# M1_Design.net
KiCad netlist of a schematic drawn in Altium Designer
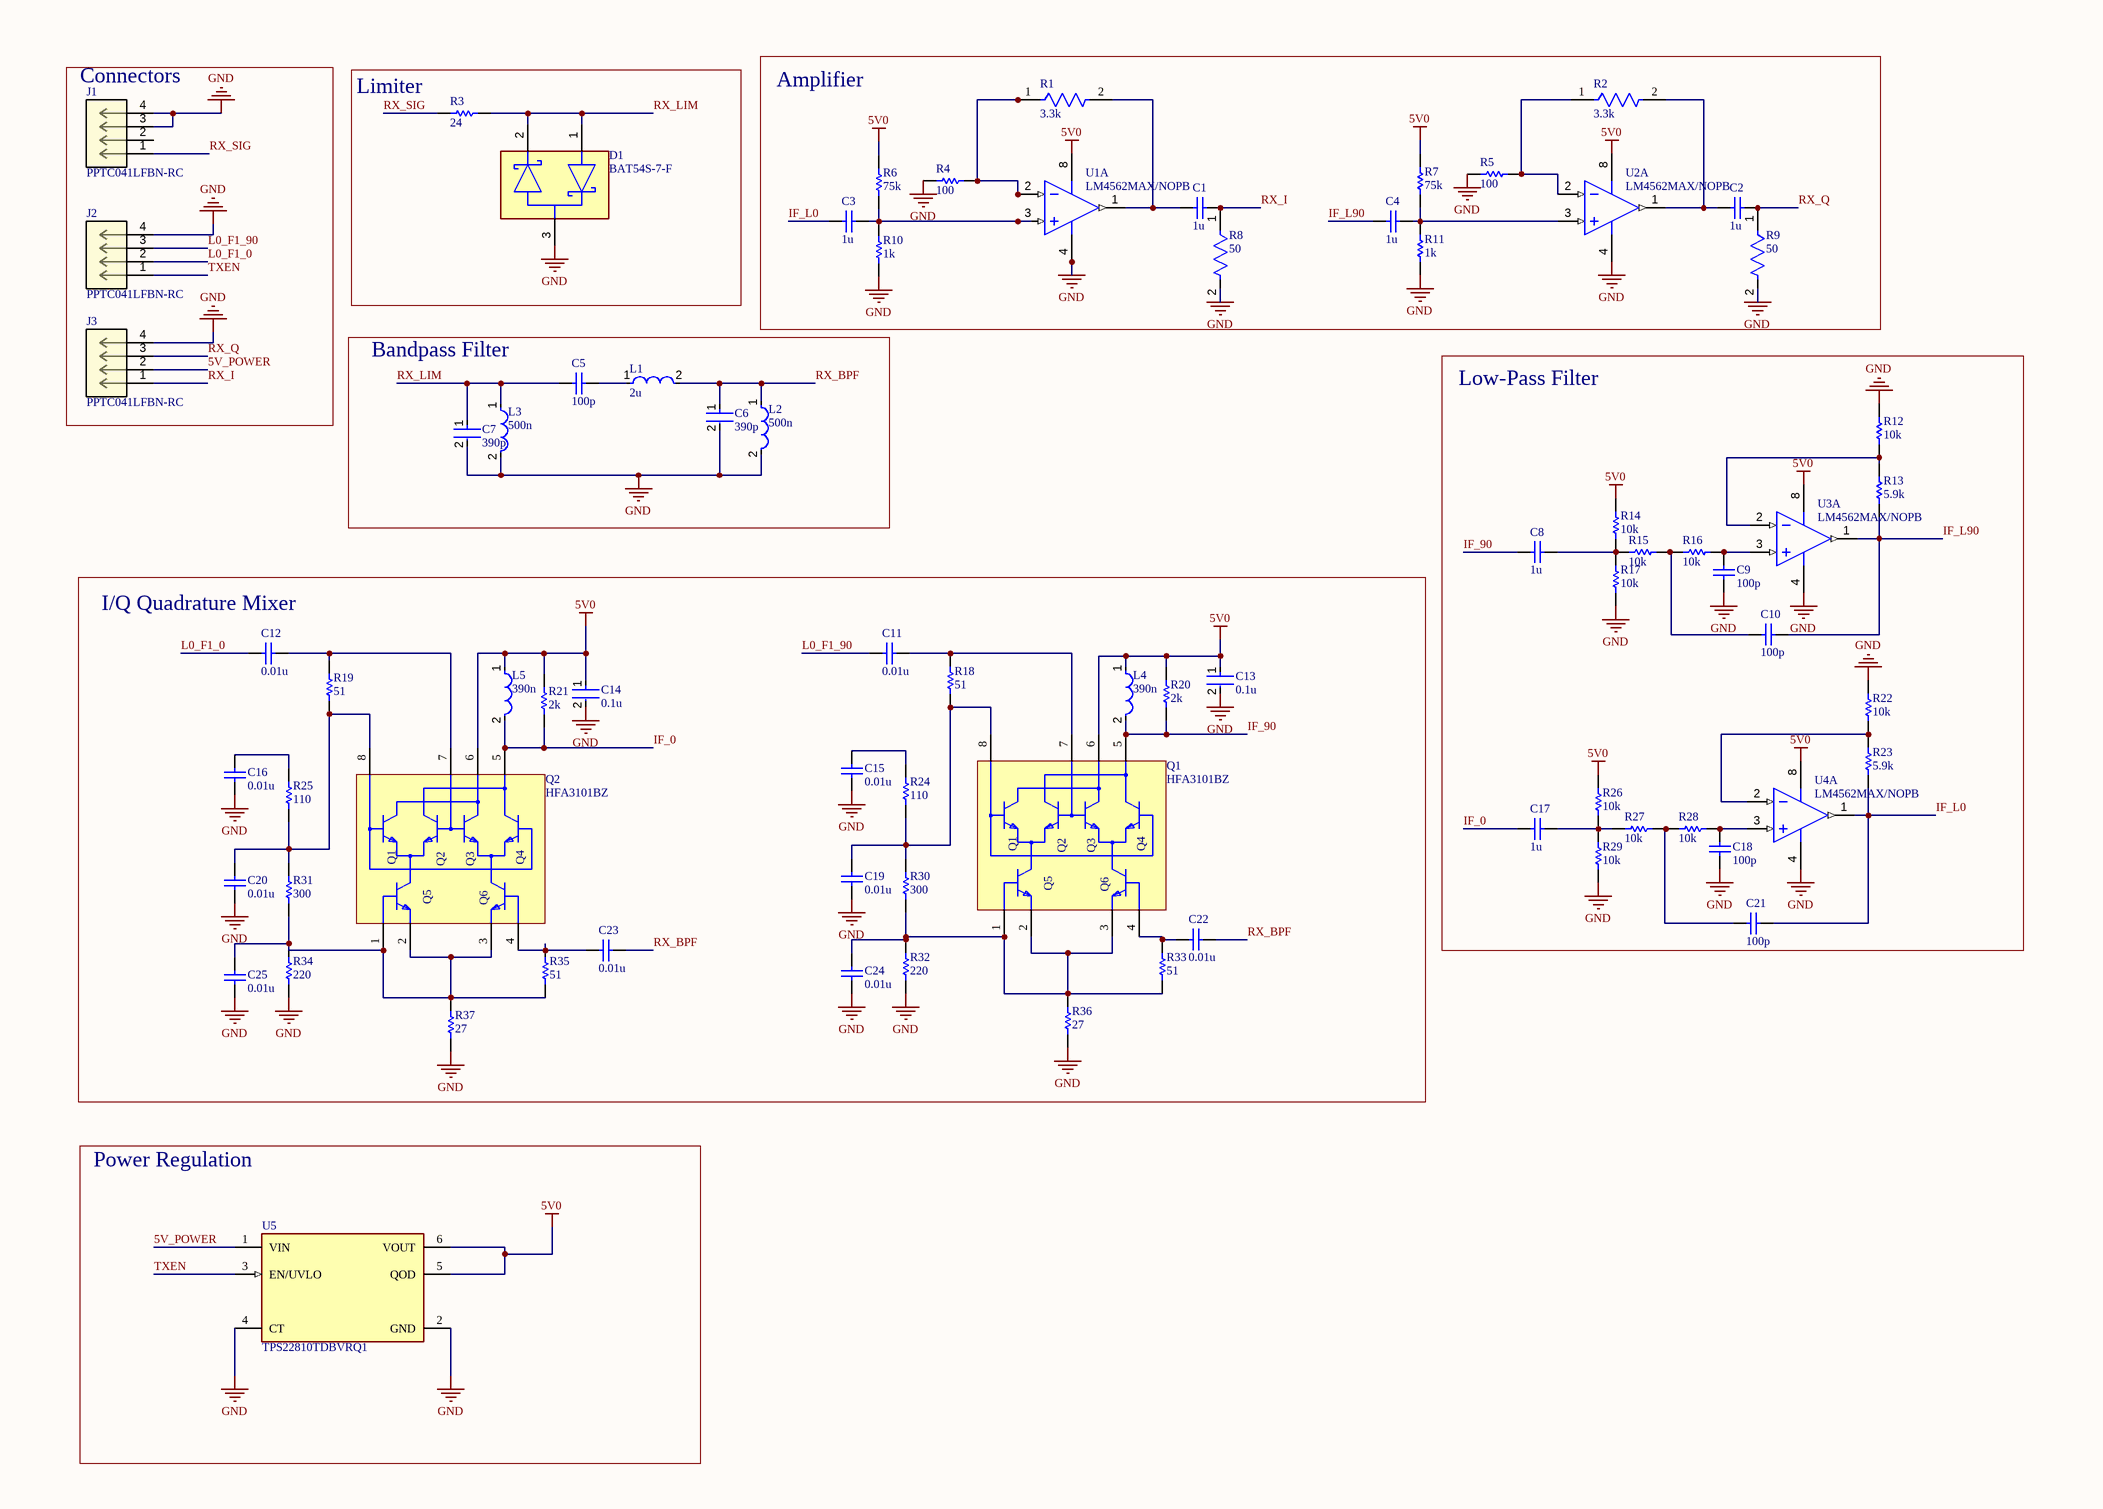
[diagram p0: M1 Design.SchDoc]

(export (version "E")
  (design (tool "Eeschema 10.0.6"))
  (components
    (comp (ref "C1")
      (value "1u")
      (footprint "CAPC3216X110X50LL20T25")
      (description "Chip Capacitor, 1 uF, +/- 10%, 50 V, -55 to 125 degC, 1206 (3216 Metric), RoHS, Tape and Reel")
      (fields (field (name "MANUFACTURER") "Kemet") (field (name "TOLERANCE") "10%"))
      (libsource (lib "Altium Content Vault") (part "CAP-NP-2"))
    )
    (comp (ref "C2")
      (value "1u")
      (footprint "CAPC3216X110X50LL20T25")
      (description "Chip Capacitor, 1 uF, +/- 10%, 50 V, -55 to 125 degC, 1206 (3216 Metric), RoHS, Tape and Reel")
      (fields (field (name "MANUFACTURER") "Kemet") (field (name "TOLERANCE") "10%"))
      (libsource (lib "Altium Content Vault") (part "CAP-NP-2"))
    )
    (comp (ref "C3")
      (value "1u")
      (footprint "CAPC3216X110X50LL20T25")
      (description "Chip Capacitor, 1 uF, +/- 10%, 50 V, -55 to 125 degC, 1206 (3216 Metric), RoHS, Tape and Reel")
      (fields (field (name "MANUFACTURER") "Kemet") (field (name "TOLERANCE") "10%"))
      (libsource (lib "Altium Content Vault") (part "CAP-NP-2"))
    )
    (comp (ref "C4")
      (value "1u")
      (footprint "CAPC3216X110X50LL20T25")
      (description "Chip Capacitor, 1 uF, +/- 10%, 50 V, -55 to 125 degC, 1206 (3216 Metric), RoHS, Tape and Reel")
      (fields (field (name "MANUFACTURER") "Kemet") (field (name "TOLERANCE") "10%"))
      (libsource (lib "Altium Content Vault") (part "CAP-NP-2"))
    )
    (comp (ref "C5")
      (value "100p")
      (footprint "CAPC1608X90X40ML10T20")
      (description "Chip Capacitor, 100 pF, +/- 5%, 50 V, -55 to 125 degC, 0603 (1608 Metric), RoHS, Tape and Reel")
      (fields (field (name "TOLERANCE") "5%") (field (name "VOLTAGE") "50V"))
      (libsource (lib "Altium Content Vault") (part "CAP-NP-2"))
    )
    (comp (ref "C6")
      (value "390p")
      (footprint "FP-GRM155-0_05-MFG")
      (description "Chip Multilayer Ceramic Capacitors for General Purpose, 0402, 390pF, C0G, 30ppm/°C, 5%, 50V")
      (fields (field (name "TOLERANCE") "5%") (field (name "VOLTAGE") "50V"))
      (libsource (lib "Altium Content Vault") (part "02cd4be3c70576c341d710602a673aa"))
    )
    (comp (ref "C7")
      (value "390p")
      (footprint "FP-GRM155-0_05-MFG")
      (description "Chip Multilayer Ceramic Capacitors for General Purpose, 0402, 390pF, C0G, 30ppm/°C, 5%, 50V")
      (fields (field (name "TOLERANCE") "5%") (field (name "VOLTAGE") "50V"))
      (libsource (lib "Altium Content Vault") (part "02cd4be3c70576c341d710602a673aa"))
    )
    (comp (ref "C8")
      (value "1u")
      (footprint "CAPC3216X110X50LL20T25")
      (description "Chip Capacitor, 1 uF, +/- 10%, 50 V, -55 to 125 degC, 1206 (3216 Metric), RoHS, Tape and Reel")
      (fields (field (name "MANUFACTURER") "Kemet") (field (name "TOLERANCE") "10%"))
      (libsource (lib "Altium Content Vault") (part "CAP-NP-2"))
    )
    (comp (ref "C9")
      (value "100p")
      (footprint "CAPC1608X90X40ML10T20")
      (description "Chip Capacitor, 100 pF, +/- 5%, 50 V, -55 to 125 degC, 0603 (1608 Metric), RoHS, Tape and Reel")
      (fields (field (name "TOLERANCE") "5%") (field (name "VOLTAGE") "50V"))
      (libsource (lib "Altium Content Vault") (part "CAP-NP-2"))
    )
    (comp (ref "C10")
      (value "100p")
      (footprint "CAPC1608X90X40ML10T20")
      (description "Chip Capacitor, 100 pF, +/- 5%, 50 V, -55 to 125 degC, 0603 (1608 Metric), RoHS, Tape and Reel")
      (fields (field (name "TOLERANCE") "5%") (field (name "VOLTAGE") "50V"))
      (libsource (lib "Altium Content Vault") (part "CAP-NP-2"))
    )
    (comp (ref "C11")
      (value "0.01u")
      (footprint "CAPC1005X55X25LL05T10")
      (description "Chip Capacitor, 10 nF, 16 V, 10%, -55 to 125 degC, 0402 (1005 Metric), RoHS, Tape and Reel")
      (fields (field (name "MANUFACTURER") "Murata"))
      (libsource (lib "Altium Content Vault") (part "CAP-NP-2"))
    )
    (comp (ref "C12")
      (value "0.01u")
      (footprint "CAPC1005X55X25LL05T10")
      (description "Chip Capacitor, 10 nF, 16 V, 10%, -55 to 125 degC, 0402 (1005 Metric), RoHS, Tape and Reel")
      (fields (field (name "MANUFACTURER") "Murata"))
      (libsource (lib "Altium Content Vault") (part "CAP-NP-2"))
    )
    (comp (ref "C13")
      (value "0.1u")
      (footprint "FP-CL17-IPC_C")
      (description "Cap Ceramic 100nF 10V X7R ±10% SMD 0402 +125°C Paper T/R")
      (fields (field (name "TOLERANCE") "10%"))
      (libsource (lib "Altium Content Vault") (part "b4654b650e69147ec39a6b967a45e02"))
    )
    (comp (ref "C14")
      (value "0.1u")
      (footprint "FP-CL17-IPC_C")
      (description "Cap Ceramic 100nF 10V X7R ±10% SMD 0402 +125°C Paper T/R")
      (fields (field (name "TOLERANCE") "10%"))
      (libsource (lib "Altium Content Vault") (part "b4654b650e69147ec39a6b967a45e02"))
    )
    (comp (ref "C15")
      (value "0.01u")
      (footprint "CAPC1005X55X25LL05T10")
      (description "Chip Capacitor, 10 nF, 16 V, 10%, -55 to 125 degC, 0402 (1005 Metric), RoHS, Tape and Reel")
      (fields (field (name "MANUFACTURER") "Murata"))
      (libsource (lib "Altium Content Vault") (part "CAP-NP-2"))
    )
    (comp (ref "C16")
      (value "0.01u")
      (footprint "CAPC1005X55X25LL05T10")
      (description "Chip Capacitor, 10 nF, 16 V, 10%, -55 to 125 degC, 0402 (1005 Metric), RoHS, Tape and Reel")
      (fields (field (name "MANUFACTURER") "Murata"))
      (libsource (lib "Altium Content Vault") (part "CAP-NP-2"))
    )
    (comp (ref "C17")
      (value "1u")
      (footprint "CAPC3216X110X50LL20T25")
      (description "Chip Capacitor, 1 uF, +/- 10%, 50 V, -55 to 125 degC, 1206 (3216 Metric), RoHS, Tape and Reel")
      (fields (field (name "MANUFACTURER") "Kemet") (field (name "TOLERANCE") "10%"))
      (libsource (lib "Altium Content Vault") (part "CAP-NP-2"))
    )
    (comp (ref "C18")
      (value "100p")
      (footprint "CAPC1608X90X40ML10T20")
      (description "Chip Capacitor, 100 pF, +/- 5%, 50 V, -55 to 125 degC, 0603 (1608 Metric), RoHS, Tape and Reel")
      (fields (field (name "TOLERANCE") "5%") (field (name "VOLTAGE") "50V"))
      (libsource (lib "Altium Content Vault") (part "CAP-NP-2"))
    )
    (comp (ref "C19")
      (value "0.01u")
      (footprint "CAPC1005X55X25LL05T10")
      (description "Chip Capacitor, 10 nF, 16 V, 10%, -55 to 125 degC, 0402 (1005 Metric), RoHS, Tape and Reel")
      (fields (field (name "MANUFACTURER") "Murata"))
      (libsource (lib "Altium Content Vault") (part "CAP-NP-2"))
    )
    (comp (ref "C20")
      (value "0.01u")
      (footprint "CAPC1005X55X25LL05T10")
      (description "Chip Capacitor, 10 nF, 16 V, 10%, -55 to 125 degC, 0402 (1005 Metric), RoHS, Tape and Reel")
      (fields (field (name "MANUFACTURER") "Murata"))
      (libsource (lib "Altium Content Vault") (part "CAP-NP-2"))
    )
    (comp (ref "C21")
      (value "100p")
      (footprint "CAPC1608X90X40ML10T20")
      (description "Chip Capacitor, 100 pF, +/- 5%, 50 V, -55 to 125 degC, 0603 (1608 Metric), RoHS, Tape and Reel")
      (fields (field (name "TOLERANCE") "5%") (field (name "VOLTAGE") "50V"))
      (libsource (lib "Altium Content Vault") (part "CAP-NP-2"))
    )
    (comp (ref "C22")
      (value "0.01u")
      (footprint "CAPC1005X55X25LL05T10")
      (description "Chip Capacitor, 10 nF, 16 V, 10%, -55 to 125 degC, 0402 (1005 Metric), RoHS, Tape and Reel")
      (fields (field (name "MANUFACTURER") "Murata"))
      (libsource (lib "Altium Content Vault") (part "CAP-NP-2"))
    )
    (comp (ref "C23")
      (value "0.01u")
      (footprint "CAPC1005X55X25LL05T10")
      (description "Chip Capacitor, 10 nF, 16 V, 10%, -55 to 125 degC, 0402 (1005 Metric), RoHS, Tape and Reel")
      (fields (field (name "MANUFACTURER") "Murata"))
      (libsource (lib "Altium Content Vault") (part "CAP-NP-2"))
    )
    (comp (ref "C24")
      (value "0.01u")
      (footprint "CAPC1005X55X25LL05T10")
      (description "Chip Capacitor, 10 nF, 16 V, 10%, -55 to 125 degC, 0402 (1005 Metric), RoHS, Tape and Reel")
      (fields (field (name "MANUFACTURER") "Murata"))
      (libsource (lib "Altium Content Vault") (part "CAP-NP-2"))
    )
    (comp (ref "C25")
      (value "0.01u")
      (footprint "CAPC1005X55X25LL05T10")
      (description "Chip Capacitor, 10 nF, 16 V, 10%, -55 to 125 degC, 0402 (1005 Metric), RoHS, Tape and Reel")
      (fields (field (name "MANUFACTURER") "Murata"))
      (libsource (lib "Altium Content Vault") (part "CAP-NP-2"))
    )
    (comp (ref "D1")
      (value "BAT54S-7-F")
      (footprint "FP-SOT23-MFG")
      (description "DIODE ARRAY SCHOTTKY 30V SOT23-3")
      (libsource (lib "Altium Content Vault") (part "835e4e71cf852b8cae3cf70bf14abf8"))
    )
    (comp (ref "J1")
      (value "PPTC041LFBN-RC")
      (footprint "CONN_PPTC041LFBN-RC_SUL")
      (description "No Description Available")
      (libsource (lib "PPTC041LFBN-RC") (part "PPTC041LFBN-RC"))
    )
    (comp (ref "J2")
      (value "PPTC041LFBN-RC")
      (footprint "CONN_PPTC041LFBN-RC_SUL")
      (description "No Description Available")
      (libsource (lib "PPTC041LFBN-RC") (part "PPTC041LFBN-RC"))
    )
    (comp (ref "J3")
      (value "PPTC041LFBN-RC")
      (footprint "CONN_PPTC041LFBN-RC_SUL")
      (description "No Description Available")
      (libsource (lib "PPTC041LFBN-RC") (part "PPTC041LFBN-RC"))
    )
    (comp (ref "L1")
      (value "2u")
      (footprint "FP-LQW15CA_00-MFG")
      (description "Wire Wound Ferrite Inductor for General Circuits 2000nH ±10% 130mA 3.2Ω 0402 (1005)")
      (fields (field (name "TOLERANCE") "10%"))
      (libsource (lib "Altium Content Vault") (part "725321dda6339637d4d059423bc1c3c"))
    )
    (comp (ref "L2")
      (value "500n")
      (footprint "FP-LQW15CA_00-MFG")
      (description "Wire Wound Ferrite Inductor for General Circuits 500nH ±5% 270mA 0.97Ω 0402 (1005)")
      (fields (field (name "TOLERANCE") "5%"))
      (libsource (lib "Altium Content Vault") (part "725321dda6339637d4d059423bc1c3c"))
    )
    (comp (ref "L3")
      (value "500n")
      (footprint "FP-LQW15CA_00-MFG")
      (description "Wire Wound Ferrite Inductor for General Circuits 500nH ±5% 270mA 0.97Ω 0402 (1005)")
      (fields (field (name "TOLERANCE") "5%"))
      (libsource (lib "Altium Content Vault") (part "725321dda6339637d4d059423bc1c3c"))
    )
    (comp (ref "L4")
      (value "390n")
      (footprint "FP-LQW18AN_00-MFG")
      (description "Wire Wound RF Inductor 390nH ±5% 80mA 6.2Ω 0603 (1608)")
      (fields (field (name "TOLERANCE") "5%"))
      (libsource (lib "Altium Content Vault") (part "725321dda6339637d4d059423bc1c3c"))
    )
    (comp (ref "L5")
      (value "390n")
      (footprint "FP-LQW18AN_00-MFG")
      (description "Wire Wound RF Inductor 390nH ±5% 80mA 6.2Ω 0603 (1608)")
      (fields (field (name "TOLERANCE") "5%"))
      (libsource (lib "Altium Content Vault") (part "725321dda6339637d4d059423bc1c3c"))
    )
    (comp (ref "Q1")
      (value "HFA3101BZ")
      (footprint "M8_15_MFG")
      (description "HFA3096 Series NPN 12 Vce 10 Ghz UHF Transistor Array - SOIC-8")
      (libsource (lib "Altium Content Vault") (part "bc79141c5fe5962b3618e6c48c8dfa3"))
    )
    (comp (ref "Q2")
      (value "HFA3101BZ")
      (footprint "M8_15_MFG")
      (description "HFA3096 Series NPN 12 Vce 10 Ghz UHF Transistor Array - SOIC-8")
      (libsource (lib "Altium Content Vault") (part "bc79141c5fe5962b3618e6c48c8dfa3"))
    )
    (comp (ref "R1")
      (value "3.3k")
      (footprint "FP-ERA2A-MFG")
      (fields (field (name "TOLERANCE") "0.1%"))
      (libsource (lib "Altium Content Vault") (part "1029c3af85768c4190bb7ad29bc67b5"))
    )
    (comp (ref "R2")
      (value "3.3k")
      (footprint "FP-ERA2A-MFG")
      (fields (field (name "TOLERANCE") "0.1%"))
      (libsource (lib "Altium Content Vault") (part "1029c3af85768c4190bb7ad29bc67b5"))
    )
    (comp (ref "R3")
      (value "24")
      (footprint "RESC1005X40X25LL05T10")
      (fields (field (name "PART NUMBER") "RC0402JR-0724RL") (field (name "MANUFACTURER") "Yageo"))
      (libsource (lib "Altium Content Vault") (part "RES"))
    )
    (comp (ref "R4")
      (value "100")
      (footprint "RESC1005X40X25NL05T10")
      (fields (field (name "PART NUMBER") "RC0402JR-07100RL") (field (name "MANUFACTURER") "Yageo / Phycomp"))
      (libsource (lib "Altium Content Vault") (part "RES"))
    )
    (comp (ref "R5")
      (value "100")
      (footprint "RESC1005X40X25NL05T10")
      (fields (field (name "PART NUMBER") "RC0402JR-07100RL") (field (name "MANUFACTURER") "Yageo / Phycomp"))
      (libsource (lib "Altium Content Vault") (part "RES"))
    )
    (comp (ref "R6")
      (value "75k")
      (footprint "RESC1005X40X25NL10T10")
      (fields (field (name "PART NUMBER") "ERA-2AEB753X") (field (name "MANUFACTURER") "Panasonic"))
      (libsource (lib "Altium Content Vault") (part "RES"))
    )
    (comp (ref "R7")
      (value "75k")
      (footprint "RESC1005X40X25NL10T10")
      (fields (field (name "PART NUMBER") "ERA-2AEB753X") (field (name "MANUFACTURER") "Panasonic"))
      (libsource (lib "Altium Content Vault") (part "RES"))
    )
    (comp (ref "R8")
      (value "50")
      (footprint "FP-ALN2512-MFG")
      (description "2512 CHIP ALNI 50 OHMS 1%")
      (libsource (lib "Altium Content Vault") (part "1029c3af85768c4190bb7ad29bc67b5"))
    )
    (comp (ref "R9")
      (value "50")
      (footprint "FP-ALN2512-MFG")
      (description "2512 CHIP ALNI 50 OHMS 1%")
      (libsource (lib "Altium Content Vault") (part "1029c3af85768c4190bb7ad29bc67b5"))
    )
    (comp (ref "R10")
      (value "1k")
      (footprint "RESC1005X40X25LL05T10")
      (fields (field (name "PART NUMBER") "RC0402JR-071KL") (field (name "MANUFACTURER") "Yageo / Phycomp"))
      (libsource (lib "Altium Content Vault") (part "RES"))
    )
    (comp (ref "R11")
      (value "1k")
      (footprint "RESC1005X40X25LL05T10")
      (fields (field (name "PART NUMBER") "RC0402JR-071KL") (field (name "MANUFACTURER") "Yageo / Phycomp"))
      (libsource (lib "Altium Content Vault") (part "RES"))
    )
    (comp (ref "R12")
      (value "10k")
      (footprint "RESC1005X40X25LL05T10")
      (fields (field (name "PART NUMBER") "RC0402FR-0710KL") (field (name "MANUFACTURER") "Yageo / Phycomp"))
      (libsource (lib "Altium Content Vault") (part "RES"))
    )
    (comp (ref "R13")
      (value "5.9k")
      (footprint "RESC1608X55X30LL15T15")
      (fields (field (name "PART NUMBER") "ERJ-3EKF5901V") (field (name "MANUFACTURER") "Panasonic"))
      (libsource (lib "Altium Content Vault") (part "RES"))
    )
    (comp (ref "R14")
      (value "10k")
      (footprint "RESC1005X40X25LL05T10")
      (fields (field (name "PART NUMBER") "RC0402FR-0710KL") (field (name "MANUFACTURER") "Yageo / Phycomp"))
      (libsource (lib "Altium Content Vault") (part "RES"))
    )
    (comp (ref "R15")
      (value "10k")
      (footprint "RESC1005X40X25LL05T10")
      (fields (field (name "PART NUMBER") "RC0402FR-0710KL") (field (name "MANUFACTURER") "Yageo / Phycomp"))
      (libsource (lib "Altium Content Vault") (part "RES"))
    )
    (comp (ref "R16")
      (value "10k")
      (footprint "RESC1005X40X25LL05T10")
      (fields (field (name "PART NUMBER") "RC0402FR-0710KL") (field (name "MANUFACTURER") "Yageo / Phycomp"))
      (libsource (lib "Altium Content Vault") (part "RES"))
    )
    (comp (ref "R17")
      (value "10k")
      (footprint "RESC1005X40X25LL05T10")
      (fields (field (name "PART NUMBER") "RC0402FR-0710KL") (field (name "MANUFACTURER") "Yageo / Phycomp"))
      (libsource (lib "Altium Content Vault") (part "RES"))
    )
    (comp (ref "R18")
      (value "51")
      (footprint "RESC1005X40X25ML05T10")
      (fields (field (name "MANUFACTURER") "Yageo / Phycomp") (field (name "PART NUMBER") "RC0402JR-0751RL"))
      (libsource (lib "Altium Content Vault") (part "RES"))
    )
    (comp (ref "R19")
      (value "51")
      (footprint "RESC1005X40X25ML05T10")
      (fields (field (name "MANUFACTURER") "Yageo / Phycomp") (field (name "PART NUMBER") "RC0402JR-0751RL"))
      (libsource (lib "Altium Content Vault") (part "RES"))
    )
    (comp (ref "R20")
      (value "2k")
      (footprint "RESC1005X40X25LL10T10")
      (fields (field (name "MANUFACTURER") "Panasonic") (field (name "PART NUMBER") "ERA-2AEB202X"))
      (libsource (lib "Altium Content Vault") (part "RES"))
    )
    (comp (ref "R21")
      (value "2k")
      (footprint "RESC1005X40X25LL10T10")
      (fields (field (name "MANUFACTURER") "Panasonic") (field (name "PART NUMBER") "ERA-2AEB202X"))
      (libsource (lib "Altium Content Vault") (part "RES"))
    )
    (comp (ref "R22")
      (value "10k")
      (footprint "RESC1005X40X25LL05T10")
      (fields (field (name "PART NUMBER") "RC0402FR-0710KL") (field (name "MANUFACTURER") "Yageo / Phycomp"))
      (libsource (lib "Altium Content Vault") (part "RES"))
    )
    (comp (ref "R23")
      (value "5.9k")
      (footprint "RESC1608X55X30LL15T15")
      (fields (field (name "PART NUMBER") "ERJ-3EKF5901V") (field (name "MANUFACTURER") "Panasonic"))
      (libsource (lib "Altium Content Vault") (part "RES"))
    )
    (comp (ref "R24")
      (value "110")
      (footprint "RESC1005X40X25ML05T05")
      (fields (field (name "MANUFACTURER") "Panasonic") (field (name "PART NUMBER") "ERJ-2GEJ111X"))
      (libsource (lib "Altium Content Vault") (part "RES"))
    )
    (comp (ref "R25")
      (value "110")
      (footprint "RESC1005X40X25ML05T05")
      (fields (field (name "MANUFACTURER") "Panasonic") (field (name "PART NUMBER") "ERJ-2GEJ111X"))
      (libsource (lib "Altium Content Vault") (part "RES"))
    )
    (comp (ref "R26")
      (value "10k")
      (footprint "RESC1005X40X25LL05T10")
      (fields (field (name "PART NUMBER") "RC0402FR-0710KL") (field (name "MANUFACTURER") "Yageo / Phycomp"))
      (libsource (lib "Altium Content Vault") (part "RES"))
    )
    (comp (ref "R27")
      (value "10k")
      (footprint "RESC1005X40X25LL05T10")
      (fields (field (name "PART NUMBER") "RC0402FR-0710KL") (field (name "MANUFACTURER") "Yageo / Phycomp"))
      (libsource (lib "Altium Content Vault") (part "RES"))
    )
    (comp (ref "R28")
      (value "10k")
      (footprint "RESC1005X40X25LL05T10")
      (fields (field (name "PART NUMBER") "RC0402FR-0710KL") (field (name "MANUFACTURER") "Yageo / Phycomp"))
      (libsource (lib "Altium Content Vault") (part "RES"))
    )
    (comp (ref "R29")
      (value "10k")
      (footprint "RESC1005X40X25LL05T10")
      (fields (field (name "PART NUMBER") "RC0402FR-0710KL") (field (name "MANUFACTURER") "Yageo / Phycomp"))
      (libsource (lib "Altium Content Vault") (part "RES"))
    )
    (comp (ref "R30")
      (value "300")
      (footprint "RESC1608X55X25LL10T15")
      (fields (field (name "MANUFACTURER") "Yageo"))
      (libsource (lib "Altium Content Vault") (part "RES-2"))
    )
    (comp (ref "R31")
      (value "300")
      (footprint "RESC1608X55X25LL10T15")
      (fields (field (name "MANUFACTURER") "Yageo"))
      (libsource (lib "Altium Content Vault") (part "RES-2"))
    )
    (comp (ref "R32")
      (value "220")
      (footprint "RESC1005X40X25NL05T10")
      (fields (field (name "MANUFACTURER") "Yageo / Phycomp") (field (name "PART NUMBER") "RC0402JR-07220RL"))
      (libsource (lib "Altium Content Vault") (part "RES"))
    )
    (comp (ref "R33")
      (value "51")
      (footprint "RESC1005X40X25ML05T10")
      (fields (field (name "MANUFACTURER") "Yageo / Phycomp") (field (name "PART NUMBER") "RC0402JR-0751RL"))
      (libsource (lib "Altium Content Vault") (part "RES"))
    )
    (comp (ref "R34")
      (value "220")
      (footprint "RESC1005X40X25NL05T10")
      (fields (field (name "MANUFACTURER") "Yageo / Phycomp") (field (name "PART NUMBER") "RC0402JR-07220RL"))
      (libsource (lib "Altium Content Vault") (part "RES"))
    )
    (comp (ref "R35")
      (value "51")
      (footprint "RESC1005X40X25ML05T10")
      (fields (field (name "MANUFACTURER") "Yageo / Phycomp") (field (name "PART NUMBER") "RC0402JR-0751RL"))
      (libsource (lib "Altium Content Vault") (part "RES"))
    )
    (comp (ref "R36")
      (value "27")
      (footprint "RESC1005X40X25NL05T10")
      (fields (field (name "PART NUMBER") "RC0402JR-0727RL") (field (name "MANUFACTURER") "Yageo / Phycomp"))
      (libsource (lib "Altium Content Vault") (part "RES"))
    )
    (comp (ref "R37")
      (value "27")
      (footprint "RESC1005X40X25NL05T10")
      (fields (field (name "PART NUMBER") "RC0402JR-0727RL") (field (name "MANUFACTURER") "Yageo / Phycomp"))
      (libsource (lib "Altium Content Vault") (part "RES"))
    )
    (comp (ref "U1")
      (value "LM4562MAX/NOPB")
      (footprint "D0008A_N")
      (description "Dual High Performance, High Fidelity Audio Operational Amplifier, 8-pin Narrow SOIC, Pb-Free")
      (fields (field (name "MANUFACTURER") "Texas Instruments"))
      (libsource (lib "Altium Content Vault") (part "AMP-AUDA-LM4562-8"))
    )
    (comp (ref "U2")
      (value "LM4562MAX/NOPB")
      (footprint "D0008A_N")
      (description "Dual High Performance, High Fidelity Audio Operational Amplifier, 8-pin Narrow SOIC, Pb-Free")
      (fields (field (name "MANUFACTURER") "Texas Instruments"))
      (libsource (lib "Altium Content Vault") (part "AMP-AUDA-LM4562-8"))
    )
    (comp (ref "U3")
      (value "LM4562MAX/NOPB")
      (footprint "D0008A_N")
      (description "Dual High Performance, High Fidelity Audio Operational Amplifier, 8-pin Narrow SOIC, Pb-Free")
      (fields (field (name "MANUFACTURER") "Texas Instruments"))
      (libsource (lib "Altium Content Vault") (part "AMP-AUDA-LM4562-8"))
    )
    (comp (ref "U4")
      (value "LM4562MAX/NOPB")
      (footprint "D0008A_N")
      (description "Dual High Performance, High Fidelity Audio Operational Amplifier, 8-pin Narrow SOIC, Pb-Free")
      (fields (field (name "MANUFACTURER") "Texas Instruments"))
      (libsource (lib "Altium Content Vault") (part "AMP-AUDA-LM4562-8"))
    )
    (comp (ref "U5")
      (value "TPS22810TDBVRQ1")
      (footprint "FP-DBV0006A-MFG")
      (description "IC PWR SWITCH N-CHAN 1:1 SOT23-6")
      (libsource (lib "Altium Content Vault") (part "2d4a2501f31e6718a49a06b44f8b6c7"))
    )
  )
  (nets
    (net (code "1") (name "/5V_POWER") (class "Default")
      (node (ref "J3") (pin "2") (pinfunction "2_2") (pintype "passive"))
      (node (ref "U5") (pin "1") (pinfunction "VIN_1") (pintype "power_in"))
    )
    (net (code "2") (name "/IF_0") (class "Default")
      (node (ref "C17") (pin "1") (pinfunction "1_1") (pintype "passive"))
      (node (ref "L5") (pin "2") (pinfunction "2_2") (pintype "passive"))
      (node (ref "Q2") (pin "5") (pinfunction "C2_C4_5") (pintype "passive"))
      (node (ref "R21") (pin "1") (pinfunction "1_1") (pintype "passive"))
    )
    (net (code "3") (name "/IF_90") (class "Default")
      (node (ref "C8") (pin "1") (pinfunction "1_1") (pintype "passive"))
      (node (ref "L4") (pin "2") (pinfunction "2_2") (pintype "passive"))
      (node (ref "Q1") (pin "5") (pinfunction "C2_C4_5") (pintype "passive"))
      (node (ref "R20") (pin "1") (pinfunction "1_1") (pintype "passive"))
    )
    (net (code "4") (name "/IF_L0") (class "Default")
      (node (ref "C21") (pin "2") (pinfunction "2_2") (pintype "passive"))
      (node (ref "C3") (pin "1") (pinfunction "1_1") (pintype "passive"))
      (node (ref "R23") (pin "1") (pinfunction "1_1") (pintype "passive"))
      (node (ref "U4") (pin "1") (pinfunction "OUT_A_1") (pintype "output"))
    )
    (net (code "5") (name "/IF_L90") (class "Default")
      (node (ref "C10") (pin "2") (pinfunction "2_2") (pintype "passive"))
      (node (ref "C4") (pin "1") (pinfunction "1_1") (pintype "passive"))
      (node (ref "R13") (pin "1") (pinfunction "1_1") (pintype "passive"))
      (node (ref "U3") (pin "1") (pinfunction "OUT_A_1") (pintype "output"))
    )
    (net (code "6") (name "/L0_F1_0") (class "Default")
      (node (ref "C12") (pin "1") (pinfunction "1_1") (pintype "passive"))
      (node (ref "J2") (pin "2") (pinfunction "2_2") (pintype "passive"))
    )
    (net (code "7") (name "/L0_F1_90") (class "Default")
      (node (ref "C11") (pin "1") (pinfunction "1_1") (pintype "passive"))
      (node (ref "J2") (pin "3") (pinfunction "3_3") (pintype "passive"))
    )
    (net (code "8") (name "/RX_BPF") (class "Default")
      (node (ref "C22") (pin "1") (pinfunction "1_1") (pintype "passive"))
      (node (ref "C23") (pin "1") (pinfunction "1_1") (pintype "passive"))
      (node (ref "C6") (pin "1") (pinfunction "1_1") (pintype "passive"))
      (node (ref "L1") (pin "2") (pinfunction "2_2") (pintype "passive"))
      (node (ref "L2") (pin "1") (pinfunction "1_1") (pintype "passive"))
    )
    (net (code "9") (name "/RX_I") (class "Default")
      (node (ref "C1") (pin "2") (pinfunction "2_2") (pintype "passive"))
      (node (ref "J3") (pin "1") (pinfunction "1_1") (pintype "passive"))
      (node (ref "R8") (pin "1") (pinfunction "1_1") (pintype "passive"))
    )
    (net (code "10") (name "/RX_LIM") (class "Default")
      (node (ref "C5") (pin "1") (pinfunction "1_1") (pintype "passive"))
      (node (ref "C7") (pin "1") (pinfunction "1_1") (pintype "passive"))
      (node (ref "D1") (pin "1") (pinfunction "1_1") (pintype "passive"))
      (node (ref "D1") (pin "2") (pinfunction "2_2") (pintype "passive"))
      (node (ref "L3") (pin "1") (pinfunction "1_1") (pintype "passive"))
      (node (ref "R3") (pin "2") (pinfunction "2_2") (pintype "passive"))
    )
    (net (code "11") (name "/RX_Q") (class "Default")
      (node (ref "C2") (pin "2") (pinfunction "2_2") (pintype "passive"))
      (node (ref "J3") (pin "3") (pinfunction "3_3") (pintype "passive"))
      (node (ref "R9") (pin "1") (pinfunction "1_1") (pintype "passive"))
    )
    (net (code "12") (name "/RX_SIG") (class "Default")
      (node (ref "J1") (pin "1") (pinfunction "1_1") (pintype "passive"))
      (node (ref "R3") (pin "1") (pinfunction "1_1") (pintype "passive"))
    )
    (net (code "13") (name "/TXEN") (class "Default")
      (node (ref "J2") (pin "1") (pinfunction "1_1") (pintype "passive"))
      (node (ref "U5") (pin "3") (pinfunction "EN/UVLO_3") (pintype "input"))
    )
    (net (code "14") (name "5V0") (class "Default")
      (node (ref "C13") (pin "1") (pinfunction "1_1") (pintype "passive"))
      (node (ref "C14") (pin "1") (pinfunction "1_1") (pintype "passive"))
      (node (ref "L4") (pin "1") (pinfunction "1_1") (pintype "passive"))
      (node (ref "L5") (pin "1") (pinfunction "1_1") (pintype "passive"))
      (node (ref "Q1") (pin "6") (pinfunction "C1_C3_6") (pintype "passive"))
      (node (ref "Q2") (pin "6") (pinfunction "C1_C3_6") (pintype "passive"))
      (node (ref "R14") (pin "2") (pinfunction "2_2") (pintype "passive"))
      (node (ref "R20") (pin "2") (pinfunction "2_2") (pintype "passive"))
      (node (ref "R21") (pin "2") (pinfunction "2_2") (pintype "passive"))
      (node (ref "R26") (pin "2") (pinfunction "2_2") (pintype "passive"))
      (node (ref "R6") (pin "2") (pinfunction "2_2") (pintype "passive"))
      (node (ref "R7") (pin "2") (pinfunction "2_2") (pintype "passive"))
      (node (ref "U1") (pin "8") (pinfunction "V+_8") (pintype "power_in"))
      (node (ref "U2") (pin "8") (pinfunction "V+_8") (pintype "power_in"))
      (node (ref "U3") (pin "8") (pinfunction "V+_8") (pintype "power_in"))
      (node (ref "U4") (pin "8") (pinfunction "V+_8") (pintype "power_in"))
      (node (ref "U5") (pin "5") (pinfunction "QOD_5") (pintype "passive"))
      (node (ref "U5") (pin "6") (pinfunction "VOUT_6") (pintype "passive"))
    )
    (net (code "15") (name "GND") (class "Default")
      (node (ref "C13") (pin "2") (pinfunction "2_2") (pintype "passive"))
      (node (ref "C14") (pin "2") (pinfunction "2_2") (pintype "passive"))
      (node (ref "C15") (pin "1") (pinfunction "1_1") (pintype "passive"))
      (node (ref "C16") (pin "1") (pinfunction "1_1") (pintype "passive"))
      (node (ref "C18") (pin "1") (pinfunction "1_1") (pintype "passive"))
      (node (ref "C19") (pin "1") (pinfunction "1_1") (pintype "passive"))
      (node (ref "C20") (pin "1") (pinfunction "1_1") (pintype "passive"))
      (node (ref "C24") (pin "1") (pinfunction "1_1") (pintype "passive"))
      (node (ref "C25") (pin "1") (pinfunction "1_1") (pintype "passive"))
      (node (ref "C6") (pin "2") (pinfunction "2_2") (pintype "passive"))
      (node (ref "C7") (pin "2") (pinfunction "2_2") (pintype "passive"))
      (node (ref "C9") (pin "1") (pinfunction "1_1") (pintype "passive"))
      (node (ref "D1") (pin "3") (pinfunction "3_3") (pintype "passive"))
      (node (ref "J1") (pin "3") (pinfunction "3_3") (pintype "passive"))
      (node (ref "J1") (pin "4") (pinfunction "4_4") (pintype "passive"))
      (node (ref "J2") (pin "4") (pinfunction "4_4") (pintype "passive"))
      (node (ref "J3") (pin "4") (pinfunction "4_4") (pintype "passive"))
      (node (ref "L2") (pin "2") (pinfunction "2_2") (pintype "passive"))
      (node (ref "L3") (pin "2") (pinfunction "2_2") (pintype "passive"))
      (node (ref "R10") (pin "1") (pinfunction "1_1") (pintype "passive"))
      (node (ref "R11") (pin "1") (pinfunction "1_1") (pintype "passive"))
      (node (ref "R12") (pin "2") (pinfunction "2_2") (pintype "passive"))
      (node (ref "R17") (pin "1") (pinfunction "1_1") (pintype "passive"))
      (node (ref "R22") (pin "2") (pinfunction "2_2") (pintype "passive"))
      (node (ref "R29") (pin "1") (pinfunction "1_1") (pintype "passive"))
      (node (ref "R32") (pin "1") (pinfunction "1_1") (pintype "passive"))
      (node (ref "R34") (pin "1") (pinfunction "1_1") (pintype "passive"))
      (node (ref "R36") (pin "1") (pinfunction "1_1") (pintype "passive"))
      (node (ref "R37") (pin "1") (pinfunction "1_1") (pintype "passive"))
      (node (ref "R4") (pin "1") (pinfunction "1_1") (pintype "passive"))
      (node (ref "R5") (pin "1") (pinfunction "1_1") (pintype "passive"))
      (node (ref "R8") (pin "2") (pinfunction "2_2") (pintype "passive"))
      (node (ref "R9") (pin "2") (pinfunction "2_2") (pintype "passive"))
      (node (ref "U1") (pin "4") (pinfunction "V-_4") (pintype "power_in"))
      (node (ref "U2") (pin "4") (pinfunction "V-_4") (pintype "power_in"))
      (node (ref "U3") (pin "4") (pinfunction "V-_4") (pintype "power_in"))
      (node (ref "U4") (pin "4") (pinfunction "V-_4") (pintype "power_in"))
      (node (ref "U5") (pin "2") (pinfunction "GND_2") (pintype "power_in"))
      (node (ref "U5") (pin "4") (pinfunction "CT_4") (pintype "passive"))
    )
    (net (code "16") (name "Net-(C3-Pad2)") (class "Default")
      (node (ref "C3") (pin "2") (pinfunction "2_2") (pintype "passive"))
      (node (ref "R10") (pin "2") (pinfunction "2_2") (pintype "passive"))
      (node (ref "R6") (pin "1") (pinfunction "1_1") (pintype "passive"))
      (node (ref "U1") (pin "3") (pinfunction "IN_A_3") (pintype "input"))
    )
    (net (code "17") (name "Net-(C4-Pad2)") (class "Default")
      (node (ref "C4") (pin "2") (pinfunction "2_2") (pintype "passive"))
      (node (ref "R11") (pin "2") (pinfunction "2_2") (pintype "passive"))
      (node (ref "R7") (pin "1") (pinfunction "1_1") (pintype "passive"))
      (node (ref "U2") (pin "3") (pinfunction "IN_A_3") (pintype "input"))
    )
    (net (code "18") (name "Net-(C5-Pad2)") (class "Default")
      (node (ref "C5") (pin "2") (pinfunction "2_2") (pintype "passive"))
      (node (ref "L1") (pin "1") (pinfunction "1_1") (pintype "passive"))
    )
    (net (code "19") (name "Net-(C8-Pad2)") (class "Default")
      (node (ref "C8") (pin "2") (pinfunction "2_2") (pintype "passive"))
      (node (ref "R14") (pin "1") (pinfunction "1_1") (pintype "passive"))
      (node (ref "R15") (pin "2") (pinfunction "2_2") (pintype "passive"))
      (node (ref "R17") (pin "2") (pinfunction "2_2") (pintype "passive"))
    )
    (net (code "20") (name "Net-(C9-Pad2)") (class "Default")
      (node (ref "C9") (pin "2") (pinfunction "2_2") (pintype "passive"))
      (node (ref "R16") (pin "1") (pinfunction "1_1") (pintype "passive"))
      (node (ref "U3") (pin "3") (pinfunction "IN_A_3") (pintype "input"))
    )
    (net (code "21") (name "Net-(C10-Pad1)") (class "Default")
      (node (ref "C10") (pin "1") (pinfunction "1_1") (pintype "passive"))
      (node (ref "R15") (pin "1") (pinfunction "1_1") (pintype "passive"))
      (node (ref "R16") (pin "2") (pinfunction "2_2") (pintype "passive"))
    )
    (net (code "22") (name "Net-(C15-Pad2)") (class "Default")
      (node (ref "C15") (pin "2") (pinfunction "2_2") (pintype "passive"))
      (node (ref "R24") (pin "2") (pinfunction "2_2") (pintype "passive"))
    )
    (net (code "23") (name "Net-(C16-Pad2)") (class "Default")
      (node (ref "C16") (pin "2") (pinfunction "2_2") (pintype "passive"))
      (node (ref "R25") (pin "2") (pinfunction "2_2") (pintype "passive"))
    )
    (net (code "24") (name "Net-(C17-Pad2)") (class "Default")
      (node (ref "C17") (pin "2") (pinfunction "2_2") (pintype "passive"))
      (node (ref "R26") (pin "1") (pinfunction "1_1") (pintype "passive"))
      (node (ref "R27") (pin "2") (pinfunction "2_2") (pintype "passive"))
      (node (ref "R29") (pin "2") (pinfunction "2_2") (pintype "passive"))
    )
    (net (code "25") (name "Net-(C18-Pad2)") (class "Default")
      (node (ref "C18") (pin "2") (pinfunction "2_2") (pintype "passive"))
      (node (ref "R28") (pin "1") (pinfunction "1_1") (pintype "passive"))
      (node (ref "U4") (pin "3") (pinfunction "IN_A_3") (pintype "input"))
    )
    (net (code "26") (name "Net-(C21-Pad1)") (class "Default")
      (node (ref "C21") (pin "1") (pinfunction "1_1") (pintype "passive"))
      (node (ref "R27") (pin "1") (pinfunction "1_1") (pintype "passive"))
      (node (ref "R28") (pin "2") (pinfunction "2_2") (pintype "passive"))
    )
    (net (code "27") (name "Net-(Q1-B1_B4)") (class "Default")
      (node (ref "C19") (pin "2") (pinfunction "2_2") (pintype "passive"))
      (node (ref "Q1") (pin "8") (pinfunction "B1_B4_8") (pintype "passive"))
      (node (ref "R18") (pin "1") (pinfunction "1_1") (pintype "passive"))
      (node (ref "R24") (pin "1") (pinfunction "1_1") (pintype "passive"))
      (node (ref "R30") (pin "2") (pinfunction "2_2") (pintype "passive"))
    )
    (net (code "28") (name "Net-(Q1-B2_B3)") (class "Default")
      (node (ref "C11") (pin "2") (pinfunction "2_2") (pintype "passive"))
      (node (ref "Q1") (pin "7") (pinfunction "B2_B3_7") (pintype "passive"))
      (node (ref "R18") (pin "2") (pinfunction "2_2") (pintype "passive"))
    )
    (net (code "29") (name "Net-(Q1-B5)") (class "Default")
      (node (ref "C24") (pin "2") (pinfunction "2_2") (pintype "passive"))
      (node (ref "Q1") (pin "1") (pinfunction "B5_1") (pintype "passive"))
      (node (ref "Q1") (pin "2") (pinfunction "E5_2") (pintype "passive"))
      (node (ref "Q1") (pin "3") (pinfunction "E6_3") (pintype "passive"))
      (node (ref "R30") (pin "1") (pinfunction "1_1") (pintype "passive"))
      (node (ref "R32") (pin "2") (pinfunction "2_2") (pintype "passive"))
      (node (ref "R33") (pin "1") (pinfunction "1_1") (pintype "passive"))
      (node (ref "R36") (pin "2") (pinfunction "2_2") (pintype "passive"))
    )
    (net (code "30") (name "Net-(Q1-B6)") (class "Default")
      (node (ref "C22") (pin "2") (pinfunction "2_2") (pintype "passive"))
      (node (ref "Q1") (pin "4") (pinfunction "B6_4") (pintype "passive"))
      (node (ref "R33") (pin "2") (pinfunction "2_2") (pintype "passive"))
    )
    (net (code "31") (name "Net-(Q2-B1_B4)") (class "Default")
      (node (ref "C20") (pin "2") (pinfunction "2_2") (pintype "passive"))
      (node (ref "Q2") (pin "8") (pinfunction "B1_B4_8") (pintype "passive"))
      (node (ref "R19") (pin "1") (pinfunction "1_1") (pintype "passive"))
      (node (ref "R25") (pin "1") (pinfunction "1_1") (pintype "passive"))
      (node (ref "R31") (pin "2") (pinfunction "2_2") (pintype "passive"))
    )
    (net (code "32") (name "Net-(Q2-B2_B3)") (class "Default")
      (node (ref "C12") (pin "2") (pinfunction "2_2") (pintype "passive"))
      (node (ref "Q2") (pin "7") (pinfunction "B2_B3_7") (pintype "passive"))
      (node (ref "R19") (pin "2") (pinfunction "2_2") (pintype "passive"))
    )
    (net (code "33") (name "Net-(Q2-B5)") (class "Default")
      (node (ref "C25") (pin "2") (pinfunction "2_2") (pintype "passive"))
      (node (ref "Q2") (pin "1") (pinfunction "B5_1") (pintype "passive"))
      (node (ref "Q2") (pin "2") (pinfunction "E5_2") (pintype "passive"))
      (node (ref "Q2") (pin "3") (pinfunction "E6_3") (pintype "passive"))
      (node (ref "R31") (pin "1") (pinfunction "1_1") (pintype "passive"))
      (node (ref "R34") (pin "2") (pinfunction "2_2") (pintype "passive"))
      (node (ref "R35") (pin "1") (pinfunction "1_1") (pintype "passive"))
      (node (ref "R37") (pin "2") (pinfunction "2_2") (pintype "passive"))
    )
    (net (code "34") (name "Net-(Q2-B6)") (class "Default")
      (node (ref "C23") (pin "2") (pinfunction "2_2") (pintype "passive"))
      (node (ref "Q2") (pin "4") (pinfunction "B6_4") (pintype "passive"))
      (node (ref "R35") (pin "2") (pinfunction "2_2") (pintype "passive"))
    )
    (net (code "35") (name "Net-(R1-Pad1)") (class "Default")
      (node (ref "R1") (pin "1") (pinfunction "1_1") (pintype "passive"))
      (node (ref "R4") (pin "2") (pinfunction "2_2") (pintype "passive"))
      (node (ref "U1") (pin "2") (pinfunction "IN_A_2") (pintype "input"))
    )
    (net (code "36") (name "Net-(R2-Pad1)") (class "Default")
      (node (ref "R2") (pin "1") (pinfunction "1_1") (pintype "passive"))
      (node (ref "R5") (pin "2") (pinfunction "2_2") (pintype "passive"))
      (node (ref "U2") (pin "2") (pinfunction "IN_A_2") (pintype "input"))
    )
    (net (code "37") (name "Net-(R12-Pad1)") (class "Default")
      (node (ref "R12") (pin "1") (pinfunction "1_1") (pintype "passive"))
      (node (ref "R13") (pin "2") (pinfunction "2_2") (pintype "passive"))
      (node (ref "U3") (pin "2") (pinfunction "IN_A_2") (pintype "input"))
    )
    (net (code "38") (name "Net-(R22-Pad1)") (class "Default")
      (node (ref "R22") (pin "1") (pinfunction "1_1") (pintype "passive"))
      (node (ref "R23") (pin "2") (pinfunction "2_2") (pintype "passive"))
      (node (ref "U4") (pin "2") (pinfunction "IN_A_2") (pintype "input"))
    )
    (net (code "39") (name "Net-(U1A-OUT_A)") (class "Default")
      (node (ref "C1") (pin "1") (pinfunction "1_1") (pintype "passive"))
      (node (ref "R1") (pin "2") (pinfunction "2_2") (pintype "passive"))
      (node (ref "U1") (pin "1") (pinfunction "OUT_A_1") (pintype "output"))
    )
    (net (code "40") (name "Net-(U2A-OUT_A)") (class "Default")
      (node (ref "C2") (pin "1") (pinfunction "1_1") (pintype "passive"))
      (node (ref "R2") (pin "2") (pinfunction "2_2") (pintype "passive"))
      (node (ref "U2") (pin "1") (pinfunction "OUT_A_1") (pintype "output"))
    )
    (net (code "41") (name "unconnected-(J1-Pad2)") (class "Default")
      (node (ref "J1") (pin "2") (pinfunction "2_2") (pintype "passive"))
    )
  )
)
